# Sheet1.net
KiCad netlist of a schematic drawn in Altium Designer
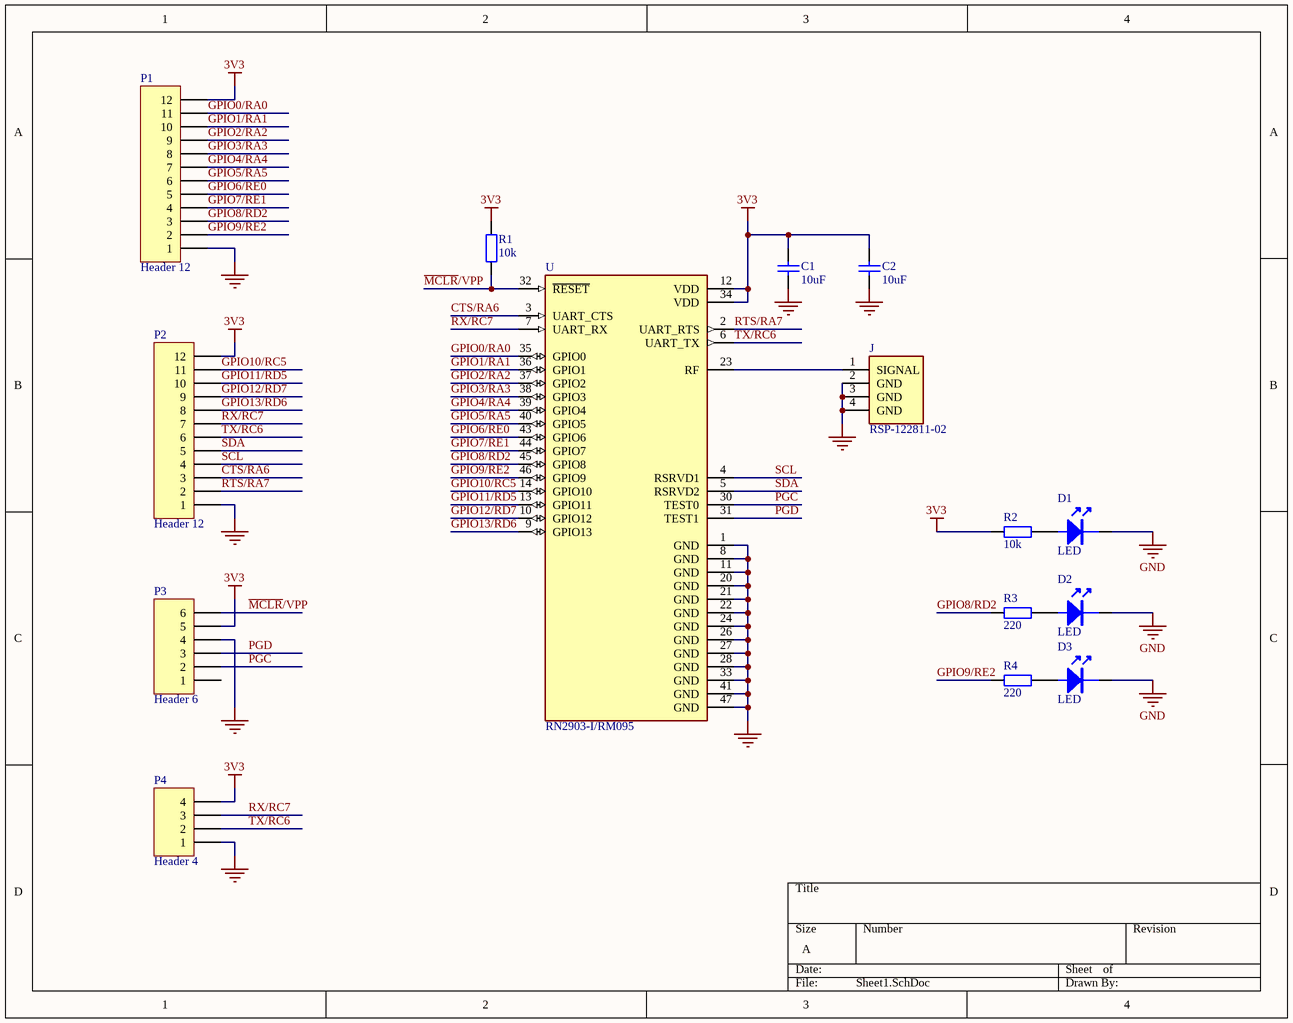
[diagram p0: Sheet1.SchDoc]

(export (version "E")
  (design (tool "Eeschema 10.0.6"))
  (components
    (comp (ref "C1")
      (value "10uF")
      (footprint "0805 CAP")
      (fields (field (name "PUBLISHER") "Altium Limited"))
      (libsource (lib "ThinhNguyenLib") (part "CAP CERAMIC"))
    )
    (comp (ref "C2")
      (value "10uF")
      (footprint "0805 CAP")
      (fields (field (name "PUBLISHER") "Altium Limited"))
      (libsource (lib "ThinhNguyenLib") (part "CAP CERAMIC"))
    )
    (comp (ref "D1") (value "LED") (footprint "LED SMD 0805") (libsource (lib "ThinhNguyenLib") (part "LED")))
    (comp (ref "D2") (value "LED") (footprint "LED SMD 0805") (libsource (lib "ThinhNguyenLib") (part "LED")))
    (comp (ref "D3") (value "LED") (footprint "LED SMD 0805") (libsource (lib "ThinhNguyenLib") (part "LED")))
    (comp (ref "J")
      (value "RSP-122811-02")
      (footprint "SAMTEC_RSP-122811-02")
      (description "IPEX MHF3 Connector Receptacle, Male Pin 50Ohm Surface Mount Solder")
      (fields (field (name "MF") "Samtec Inc."))
      (libsource (lib "RSP-122811-02") (part "RSP-122811-02"))
    )
    (comp (ref "P1")
      (value "Header 12")
      (footprint "HDR1X12")
      (description "Header, 12-Pin")
      (fields (field (name "PUBLISHER") "Altium Limited"))
      (libsource (lib "Miscellaneous Connectors") (part "Header 12"))
    )
    (comp (ref "P2")
      (value "Header 12")
      (footprint "HDR1X12")
      (description "Header, 12-Pin")
      (fields (field (name "PUBLISHER") "Altium Limited"))
      (libsource (lib "Miscellaneous Connectors") (part "Header 12"))
    )
    (comp (ref "P3")
      (value "Header 6")
      (footprint "HDR1X6")
      (description "Header, 6-Pin")
      (fields (field (name "PUBLISHER") "Altium Limited"))
      (libsource (lib "Miscellaneous Connectors") (part "Header 6"))
    )
    (comp (ref "P4")
      (value "Header 4")
      (footprint "HDR1X4")
      (description "Header, 4-Pin")
      (fields (field (name "PUBLISHER") "Altium Limited"))
      (libsource (lib "Miscellaneous Connectors") (part "Header 4"))
    )
    (comp (ref "R1")
      (value "10k")
      (footprint "0805 RESISTOR")
      (libsource (lib "ThinhNguyenLib") (part "RESISTOR"))
    )
    (comp (ref "R2")
      (value "10k")
      (footprint "0805 RESISTOR")
      (libsource (lib "ThinhNguyenLib") (part "RESISTOR"))
    )
    (comp (ref "R3")
      (value "220")
      (footprint "0805 RESISTOR")
      (libsource (lib "ThinhNguyenLib") (part "RESISTOR"))
    )
    (comp (ref "R4")
      (value "220")
      (footprint "0805 RESISTOR")
      (libsource (lib "ThinhNguyenLib") (part "RESISTOR"))
    )
    (comp (ref "U")
      (value "RN2903-I/RM095")
      (footprint "XCVR_RN2903-I/RM095")
      (description "General ISM < 1GHz LoRaâ„¢ Transceiver Module 915MHz Antenna Not Included, SMA Surface Mount")
      (fields (field (name "MF") "Microchip"))
      (libsource (lib "RN2903-I_RM095") (part "RN2903-I/RM095"))
    )
  )
  (nets
    (net (code "1") (name "/CTS{slash}RA6") (class "Default")
      (node (ref "P2") (pin "3") (pinfunction "3_3") (pintype "passive"))
      (node (ref "U") (pin "3") (pinfunction "UART_CTS_3") (pintype "input"))
    )
    (net (code "2") (name "/GPIO0{slash}RA0") (class "Default")
      (node (ref "P1") (pin "11") (pinfunction "11_11") (pintype "passive"))
      (node (ref "U") (pin "35") (pinfunction "GPIO0_35") (pintype "bidirectional"))
    )
    (net (code "3") (name "/GPIO1{slash}RA1") (class "Default")
      (node (ref "P1") (pin "10") (pinfunction "10_10") (pintype "passive"))
      (node (ref "U") (pin "36") (pinfunction "GPIO1_36") (pintype "bidirectional"))
    )
    (net (code "4") (name "/GPIO2{slash}RA2") (class "Default")
      (node (ref "P1") (pin "9") (pinfunction "9_9") (pintype "passive"))
      (node (ref "U") (pin "37") (pinfunction "GPIO2_37") (pintype "bidirectional"))
    )
    (net (code "5") (name "/GPIO3{slash}RA3") (class "Default")
      (node (ref "P1") (pin "8") (pinfunction "8_8") (pintype "passive"))
      (node (ref "U") (pin "38") (pinfunction "GPIO3_38") (pintype "bidirectional"))
    )
    (net (code "6") (name "/GPIO4{slash}RA4") (class "Default")
      (node (ref "P1") (pin "7") (pinfunction "7_7") (pintype "passive"))
      (node (ref "U") (pin "39") (pinfunction "GPIO4_39") (pintype "bidirectional"))
    )
    (net (code "7") (name "/GPIO5{slash}RA5") (class "Default")
      (node (ref "P1") (pin "6") (pinfunction "6_6") (pintype "passive"))
      (node (ref "U") (pin "40") (pinfunction "GPIO5_40") (pintype "bidirectional"))
    )
    (net (code "8") (name "/GPIO6{slash}RE0") (class "Default")
      (node (ref "P1") (pin "5") (pinfunction "5_5") (pintype "passive"))
      (node (ref "U") (pin "43") (pinfunction "GPIO6_43") (pintype "bidirectional"))
    )
    (net (code "9") (name "/GPIO7{slash}RE1") (class "Default")
      (node (ref "P1") (pin "4") (pinfunction "4_4") (pintype "passive"))
      (node (ref "U") (pin "44") (pinfunction "GPIO7_44") (pintype "bidirectional"))
    )
    (net (code "10") (name "/GPIO8{slash}RD2") (class "Default")
      (node (ref "P1") (pin "3") (pinfunction "3_3") (pintype "passive"))
      (node (ref "R3") (pin "1") (pinfunction "1_1") (pintype "passive"))
      (node (ref "U") (pin "45") (pinfunction "GPIO8_45") (pintype "bidirectional"))
    )
    (net (code "11") (name "/GPIO9{slash}RE2") (class "Default")
      (node (ref "P1") (pin "2") (pinfunction "2_2") (pintype "passive"))
      (node (ref "R4") (pin "1") (pinfunction "1_1") (pintype "passive"))
      (node (ref "U") (pin "46") (pinfunction "GPIO9_46") (pintype "bidirectional"))
    )
    (net (code "12") (name "/GPIO10{slash}RC5") (class "Default")
      (node (ref "P2") (pin "11") (pinfunction "11_11") (pintype "passive"))
      (node (ref "U") (pin "14") (pinfunction "GPIO10_14") (pintype "bidirectional"))
    )
    (net (code "13") (name "/GPIO11{slash}RD5") (class "Default")
      (node (ref "P2") (pin "10") (pinfunction "10_10") (pintype "passive"))
      (node (ref "U") (pin "13") (pinfunction "GPIO11_13") (pintype "bidirectional"))
    )
    (net (code "14") (name "/GPIO12{slash}RD7") (class "Default")
      (node (ref "P2") (pin "9") (pinfunction "9_9") (pintype "passive"))
      (node (ref "U") (pin "10") (pinfunction "GPIO12_10") (pintype "bidirectional"))
    )
    (net (code "15") (name "/GPIO13{slash}RD6") (class "Default")
      (node (ref "P2") (pin "8") (pinfunction "8_8") (pintype "passive"))
      (node (ref "U") (pin "9") (pinfunction "GPIO13_9") (pintype "bidirectional"))
    )
    (net (code "16") (name "/PGC") (class "Default")
      (node (ref "P3") (pin "2") (pinfunction "2_2") (pintype "passive"))
      (node (ref "U") (pin "30") (pinfunction "TEST0_30") (pintype "passive"))
    )
    (net (code "17") (name "/PGD") (class "Default")
      (node (ref "P3") (pin "3") (pinfunction "3_3") (pintype "passive"))
      (node (ref "U") (pin "31") (pinfunction "TEST1_31") (pintype "passive"))
    )
    (net (code "18") (name "/RTS{slash}RA7") (class "Default")
      (node (ref "P2") (pin "2") (pinfunction "2_2") (pintype "passive"))
      (node (ref "U") (pin "2") (pinfunction "UART_RTS_2") (pintype "output"))
    )
    (net (code "19") (name "/RX{slash}RC7") (class "Default")
      (node (ref "P2") (pin "7") (pinfunction "7_7") (pintype "passive"))
      (node (ref "P4") (pin "3") (pinfunction "3_3") (pintype "passive"))
      (node (ref "U") (pin "7") (pinfunction "UART_RX_7") (pintype "input"))
    )
    (net (code "20") (name "/SCL") (class "Default")
      (node (ref "P2") (pin "4") (pinfunction "4_4") (pintype "passive"))
      (node (ref "U") (pin "4") (pinfunction "RSRVD1_4") (pintype "passive"))
    )
    (net (code "21") (name "/SDA") (class "Default")
      (node (ref "P2") (pin "5") (pinfunction "5_5") (pintype "passive"))
      (node (ref "U") (pin "5") (pinfunction "RSRVD2_5") (pintype "passive"))
    )
    (net (code "22") (name "/TX{slash}RC6") (class "Default")
      (node (ref "P2") (pin "6") (pinfunction "6_6") (pintype "passive"))
      (node (ref "P4") (pin "2") (pinfunction "2_2") (pintype "passive"))
      (node (ref "U") (pin "6") (pinfunction "UART_TX_6") (pintype "output"))
    )
    (net (code "23") (name "/~{MCLR}{slash}VPP") (class "Default")
      (node (ref "P3") (pin "6") (pinfunction "6_6") (pintype "passive"))
      (node (ref "R1") (pin "1") (pinfunction "1_1") (pintype "passive"))
      (node (ref "U") (pin "32") (pinfunction "~{RESET}_32") (pintype "input"))
    )
    (net (code "24") (name "3V3") (class "Default")
      (node (ref "C1") (pin "2") (pinfunction "2_2") (pintype "passive"))
      (node (ref "C2") (pin "2") (pinfunction "2_2") (pintype "passive"))
      (node (ref "P1") (pin "12") (pinfunction "12_12") (pintype "passive"))
      (node (ref "P2") (pin "12") (pinfunction "12_12") (pintype "passive"))
      (node (ref "P3") (pin "5") (pinfunction "5_5") (pintype "passive"))
      (node (ref "P4") (pin "4") (pinfunction "4_4") (pintype "passive"))
      (node (ref "R1") (pin "2") (pinfunction "2_2") (pintype "passive"))
      (node (ref "R2") (pin "1") (pinfunction "1_1") (pintype "passive"))
      (node (ref "U") (pin "12") (pinfunction "VDD_12") (pintype "power_in"))
      (node (ref "U") (pin "34") (pinfunction "VDD_34") (pintype "power_in"))
    )
    (net (code "25") (name "GND") (class "Default")
      (node (ref "C1") (pin "1") (pinfunction "1_1") (pintype "passive"))
      (node (ref "C2") (pin "1") (pinfunction "1_1") (pintype "passive"))
      (node (ref "D1") (pin "2") (pinfunction "2_2") (pintype "passive"))
      (node (ref "D2") (pin "2") (pinfunction "2_2") (pintype "passive"))
      (node (ref "D3") (pin "2") (pinfunction "2_2") (pintype "passive"))
      (node (ref "J") (pin "2") (pinfunction "GND_2") (pintype "power_in"))
      (node (ref "J") (pin "3") (pinfunction "GND_3") (pintype "power_in"))
      (node (ref "J") (pin "4") (pinfunction "GND_4") (pintype "power_in"))
      (node (ref "P1") (pin "1") (pinfunction "1_1") (pintype "passive"))
      (node (ref "P2") (pin "1") (pinfunction "1_1") (pintype "passive"))
      (node (ref "P3") (pin "4") (pinfunction "4_4") (pintype "passive"))
      (node (ref "P4") (pin "1") (pinfunction "1_1") (pintype "passive"))
      (node (ref "U") (pin "1") (pinfunction "GND_1") (pintype "power_in"))
      (node (ref "U") (pin "11") (pinfunction "GND_11") (pintype "power_in"))
      (node (ref "U") (pin "20") (pinfunction "GND_20") (pintype "power_in"))
      (node (ref "U") (pin "21") (pinfunction "GND_21") (pintype "power_in"))
      (node (ref "U") (pin "22") (pinfunction "GND_22") (pintype "power_in"))
      (node (ref "U") (pin "24") (pinfunction "GND_24") (pintype "power_in"))
      (node (ref "U") (pin "26") (pinfunction "GND_26") (pintype "power_in"))
      (node (ref "U") (pin "27") (pinfunction "GND_27") (pintype "power_in"))
      (node (ref "U") (pin "28") (pinfunction "GND_28") (pintype "power_in"))
      (node (ref "U") (pin "33") (pinfunction "GND_33") (pintype "power_in"))
      (node (ref "U") (pin "41") (pinfunction "GND_41") (pintype "power_in"))
      (node (ref "U") (pin "47") (pinfunction "GND_47") (pintype "power_in"))
      (node (ref "U") (pin "8") (pinfunction "GND_8") (pintype "power_in"))
    )
    (net (code "26") (name "Net-(D1-Pad1)") (class "Default")
      (node (ref "D1") (pin "1") (pinfunction "1_1") (pintype "passive"))
      (node (ref "R2") (pin "2") (pinfunction "2_2") (pintype "passive"))
    )
    (net (code "27") (name "Net-(D2-Pad1)") (class "Default")
      (node (ref "D2") (pin "1") (pinfunction "1_1") (pintype "passive"))
      (node (ref "R3") (pin "2") (pinfunction "2_2") (pintype "passive"))
    )
    (net (code "28") (name "Net-(D3-Pad1)") (class "Default")
      (node (ref "D3") (pin "1") (pinfunction "1_1") (pintype "passive"))
      (node (ref "R4") (pin "2") (pinfunction "2_2") (pintype "passive"))
    )
    (net (code "29") (name "Net-(J-SIGNAL)") (class "Default")
      (node (ref "J") (pin "1") (pinfunction "SIGNAL_1") (pintype "power_in"))
      (node (ref "U") (pin "23") (pinfunction "RF_23") (pintype "passive"))
    )
    (net (code "30") (name "unconnected-(P3-Pad1)") (class "Default")
      (node (ref "P3") (pin "1") (pinfunction "1_1") (pintype "passive"))
    )
  )
)
